# Buck_Boost_Converter.net
KiCad netlist of a schematic drawn in Altium Designer
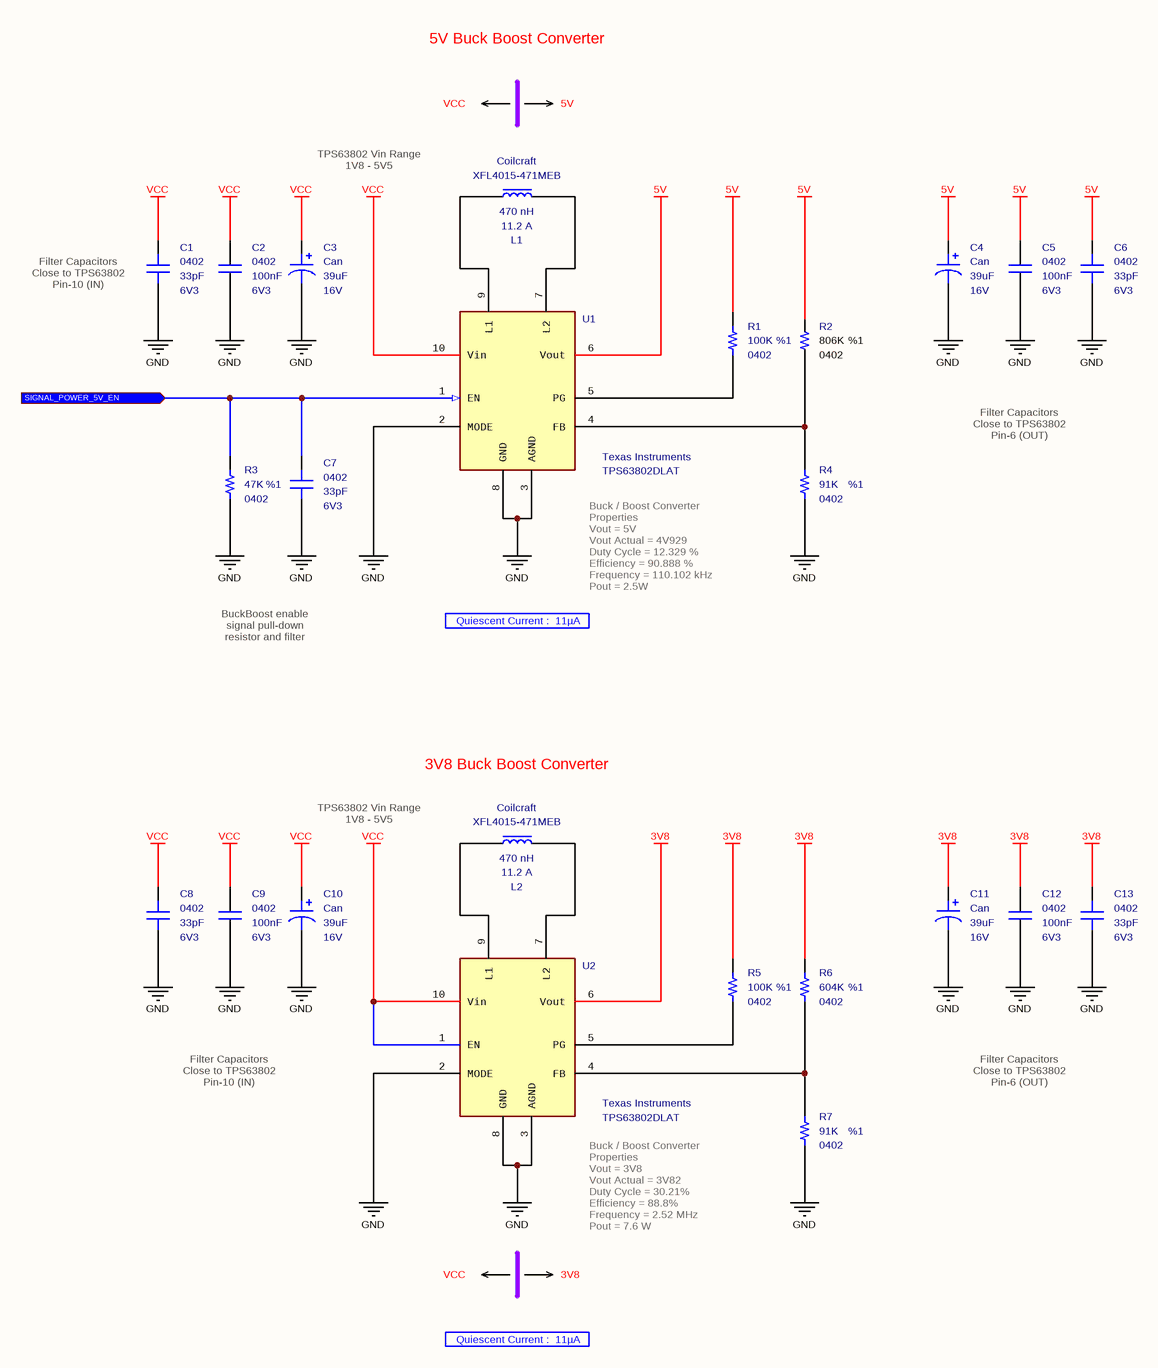
[diagram p0: Buck Boost Converter.SchDoc]

(export (version "E")
  (design (tool "Eeschema 10.0.6"))
  (components
    (comp (ref "C1")
      (value "33pF")
      (footprint "CAPACITOR_0402")
      (description "Capacitor - 33pF [0402] (Ceramic)")
      (fields
        (field (name "MANUFACTURER_PART_NUMBER") "C0402C330J9RACAUTO")
        (field (name "MOUSER_PART_NUMBER") "80-C0402C330J9RAUTO")
        (field (name "CASE") "0402")
        (field (name "VOLTAGE") "6V3")
      )
      (libsource (lib "Ovoo_Schematic") (part "Capacitor - 33pF [0402-6V3]"))
    )
    (comp (ref "C2")
      (value "100nF")
      (footprint "CAPACITOR_0402")
      (description "Capacitor - 100nF [0402-6V3] (Ceramic)")
      (fields
        (field (name "MANUFACTURER_PART_NUMBER") "04026D104KAT4A")
        (field (name "MOUSER_PART_NUMBER") "581-04026D104KAT4A")
        (field (name "CASE") "0402")
        (field (name "VOLTAGE") "6V3")
      )
      (libsource (lib "Ovoo_Schematic") (part "Capacitor - 100nF [0402-6V3]"))
    )
    (comp (ref "C3")
      (value "39uF")
      (footprint "CAPACITOR_CAN-B6")
      (description "Capacitor - 39uF 16V [Can] (Electrolytic)")
      (fields
        (field (name "MANUFACTURER_PART_NUMBER") "16SVPC39MV")
        (field (name "MOUSER_PART_NUMBER") "667-16SVPC39MV")
        (field (name "CASE") "Can")
        (field (name "VOLTAGE") "16V")
      )
      (libsource (lib "Ovoo_Schematic") (part "Capacitor - 39uF [Can-16V]"))
    )
    (comp (ref "C4")
      (value "39uF")
      (footprint "CAPACITOR_CAN-B6")
      (description "Capacitor - 39uF 16V [Can] (Electrolytic)")
      (fields
        (field (name "MANUFACTURER_PART_NUMBER") "16SVPC39MV")
        (field (name "MOUSER_PART_NUMBER") "667-16SVPC39MV")
        (field (name "CASE") "Can")
        (field (name "VOLTAGE") "16V")
      )
      (libsource (lib "Ovoo_Schematic") (part "Capacitor - 39uF [Can-16V]"))
    )
    (comp (ref "C5")
      (value "100nF")
      (footprint "CAPACITOR_0402")
      (description "Capacitor - 100nF [0402-6V3] (Ceramic)")
      (fields
        (field (name "MANUFACTURER_PART_NUMBER") "04026D104KAT4A")
        (field (name "MOUSER_PART_NUMBER") "581-04026D104KAT4A")
        (field (name "CASE") "0402")
        (field (name "VOLTAGE") "6V3")
      )
      (libsource (lib "Ovoo_Schematic") (part "Capacitor - 100nF [0402-6V3]"))
    )
    (comp (ref "C6")
      (value "33pF")
      (footprint "CAPACITOR_0402")
      (description "Capacitor - 33pF [0402] (Ceramic)")
      (fields
        (field (name "MANUFACTURER_PART_NUMBER") "C0402C330J9RACAUTO")
        (field (name "MOUSER_PART_NUMBER") "80-C0402C330J9RAUTO")
        (field (name "CASE") "0402")
        (field (name "VOLTAGE") "6V3")
      )
      (libsource (lib "Ovoo_Schematic") (part "Capacitor - 33pF [0402-6V3]"))
    )
    (comp (ref "C7")
      (value "33pF")
      (footprint "CAPACITOR_0402")
      (description "Capacitor - 33pF [0402] (Ceramic)")
      (fields
        (field (name "MANUFACTURER_PART_NUMBER") "C0402C330J9RACAUTO")
        (field (name "MOUSER_PART_NUMBER") "80-C0402C330J9RAUTO")
        (field (name "CASE") "0402")
        (field (name "VOLTAGE") "6V3")
      )
      (libsource (lib "Ovoo_Schematic") (part "Capacitor - 33pF [0402-6V3]"))
    )
    (comp (ref "C8")
      (value "33pF")
      (footprint "CAPACITOR_0402")
      (description "Capacitor - 33pF [0402] (Ceramic)")
      (fields
        (field (name "MANUFACTURER_PART_NUMBER") "C0402C330J9RACAUTO")
        (field (name "MOUSER_PART_NUMBER") "80-C0402C330J9RAUTO")
        (field (name "CASE") "0402")
        (field (name "VOLTAGE") "6V3")
      )
      (libsource (lib "Ovoo_Schematic") (part "Capacitor - 33pF [0402-6V3]"))
    )
    (comp (ref "C9")
      (value "100nF")
      (footprint "CAPACITOR_0402")
      (description "Capacitor - 100nF [0402-6V3] (Ceramic)")
      (fields
        (field (name "MANUFACTURER_PART_NUMBER") "04026D104KAT4A")
        (field (name "MOUSER_PART_NUMBER") "581-04026D104KAT4A")
        (field (name "CASE") "0402")
        (field (name "VOLTAGE") "6V3")
      )
      (libsource (lib "Ovoo_Schematic") (part "Capacitor - 100nF [0402-6V3]"))
    )
    (comp (ref "C10")
      (value "39uF")
      (footprint "CAPACITOR_CAN-B6")
      (description "Capacitor - 39uF 16V [Can] (Electrolytic)")
      (fields
        (field (name "MANUFACTURER_PART_NUMBER") "16SVPC39MV")
        (field (name "MOUSER_PART_NUMBER") "667-16SVPC39MV")
        (field (name "CASE") "Can")
        (field (name "VOLTAGE") "16V")
      )
      (libsource (lib "Ovoo_Schematic") (part "Capacitor - 39uF [Can-16V]"))
    )
    (comp (ref "C11")
      (value "39uF")
      (footprint "CAPACITOR_CAN-B6")
      (description "Capacitor - 39uF 16V [Can] (Electrolytic)")
      (fields
        (field (name "MANUFACTURER_PART_NUMBER") "16SVPC39MV")
        (field (name "MOUSER_PART_NUMBER") "667-16SVPC39MV")
        (field (name "CASE") "Can")
        (field (name "VOLTAGE") "16V")
      )
      (libsource (lib "Ovoo_Schematic") (part "Capacitor - 39uF [Can-16V]"))
    )
    (comp (ref "C12")
      (value "100nF")
      (footprint "CAPACITOR_0402")
      (description "Capacitor - 100nF [0402-6V3] (Ceramic)")
      (fields
        (field (name "MANUFACTURER_PART_NUMBER") "04026D104KAT4A")
        (field (name "MOUSER_PART_NUMBER") "581-04026D104KAT4A")
        (field (name "CASE") "0402")
        (field (name "VOLTAGE") "6V3")
      )
      (libsource (lib "Ovoo_Schematic") (part "Capacitor - 100nF [0402-6V3]"))
    )
    (comp (ref "C13")
      (value "33pF")
      (footprint "CAPACITOR_0402")
      (description "Capacitor - 33pF [0402] (Ceramic)")
      (fields
        (field (name "MANUFACTURER_PART_NUMBER") "C0402C330J9RACAUTO")
        (field (name "MOUSER_PART_NUMBER") "80-C0402C330J9RAUTO")
        (field (name "CASE") "0402")
        (field (name "VOLTAGE") "6V3")
      )
      (libsource (lib "Ovoo_Schematic") (part "Capacitor - 33pF [0402-6V3]"))
    )
    (comp (ref "L1")
      (value "470 nH")
      (footprint "INDUCTOR_XFL4015")
      (description "Fixed Inductors 0.47uH 20% 11.2A 8.36mOhms AEC-Q200")
      (fields
        (field (name "MOUSER_PART_NUMBER") "994-XFL4015-471MEB")
        (field (name "TOLERANCE") "20%")
        (field (name "MAXIMUM DC CURRENT") "11.2 A")
        (field (name "MANUFACTURER_PART_NUMBER") "XFL4015-471MEB")
        (field (name "MANUFACTURER_NAME") "Coilcraft")
      )
      (libsource (lib "Ovoo_Schematic") (part "Inductor - 470 nH [SMD]"))
    )
    (comp (ref "L2")
      (value "470 nH")
      (footprint "INDUCTOR_XFL4015")
      (description "Fixed Inductors 0.47uH 20% 11.2A 8.36mOhms AEC-Q200")
      (fields
        (field (name "MOUSER_PART_NUMBER") "994-XFL4015-471MEB")
        (field (name "TOLERANCE") "20%")
        (field (name "MAXIMUM DC CURRENT") "11.2 A")
        (field (name "MANUFACTURER_PART_NUMBER") "XFL4015-471MEB")
        (field (name "MANUFACTURER_NAME") "Coilcraft")
      )
      (libsource (lib "Ovoo_Schematic") (part "Inductor - 470 nH [SMD]"))
    )
    (comp (ref "R1")
      (value "100K")
      (footprint "RESISTOR_0402")
      (description "Thick Film Resistors - SMD 1/16 W 100 Kohms 1%")
      (fields
        (field (name "MANUFACTURER_PART_NUMBER") "CRCW0402100KFKED")
        (field (name "MOUSER_PART_NUMBER") "71-CRCW0402-100K-E3")
        (field (name "TOLERANCE") "%1")
        (field (name "CASE") "0402")
      )
      (libsource (lib "Ovoo_Schematic") (part "Resistor - 100K"))
    )
    (comp (ref "R2")
      (value "806K")
      (footprint "RESISTOR_0402")
      (description "Thick Film Resistors - SMD 1/16 W 806 Kohms 1%")
      (fields
        (field (name "TOLERANCE") "%1")
        (field (name "CASE") "0402")
        (field (name "MANUFACTURER PART NUMBER") "CRCW0402806KFKED")
        (field (name "MOUSER PART NUMBER") "71-CRCW0402-806K-E3")
      )
      (libsource (lib "Ovoo_Library") (part "Resistor - 806K"))
    )
    (comp (ref "R3")
      (value "47K")
      (footprint "RESISTOR_0402")
      (description "Thick Film Resistors - SMD 1/16 W 47 Kohms 1%")
      (fields
        (field (name "MANUFACTURER_PART_NUMBER") "CRCW040247K0FKED")
        (field (name "MOUSER_PART_NUMBER") "71-CRCW0402-47K-E3")
        (field (name "TOLERANCE") "%1")
        (field (name "CASE") "0402")
      )
      (libsource (lib "Ovoo_Schematic") (part "Resistor - 47K"))
    )
    (comp (ref "R4")
      (value "91K")
      (footprint "RESISTOR_0402")
      (description "Thick Film Resistors - SMD 1/16 W 91 Kohms 1%")
      (fields
        (field (name "MANUFACTURER_PART_NUMBER") "CRCW040291K0FKED")
        (field (name "MOUSER_PART_NUMBER") "71-CRCW040291K0FKED")
        (field (name "TOLERANCE") "%1")
        (field (name "CASE") "0402")
      )
      (libsource (lib "Ovoo_Schematic") (part "Resistor - 91K"))
    )
    (comp (ref "R5")
      (value "100K")
      (footprint "RESISTOR_0402")
      (description "Thick Film Resistors - SMD 1/16 W 100 Kohms 1%")
      (fields
        (field (name "MANUFACTURER_PART_NUMBER") "CRCW0402100KFKED")
        (field (name "MOUSER_PART_NUMBER") "71-CRCW0402-100K-E3")
        (field (name "TOLERANCE") "%1")
        (field (name "CASE") "0402")
      )
      (libsource (lib "Ovoo_Schematic") (part "Resistor - 100K"))
    )
    (comp (ref "R6")
      (value "604K")
      (footprint "RESISTOR_0402")
      (description "Thick Film Resistors - SMD 1/16 W 604 Kohms 1%")
      (fields
        (field (name "MANUFACTURER_PART_NUMBER") "CRCW0402604KFKED")
        (field (name "MOUSER_PART_NUMBER") "71-CRCW0402-604K-E3")
        (field (name "TOLERANCE") "%1")
        (field (name "CASE") "0402")
      )
      (libsource (lib "Ovoo_Schematic") (part "Resistor - 604K"))
    )
    (comp (ref "R7")
      (value "91K")
      (footprint "RESISTOR_0402")
      (description "Thick Film Resistors - SMD 1/16 W 91 Kohms 1%")
      (fields
        (field (name "MANUFACTURER_PART_NUMBER") "CRCW040291K0FKED")
        (field (name "MOUSER_PART_NUMBER") "71-CRCW040291K0FKED")
        (field (name "TOLERANCE") "%1")
        (field (name "CASE") "0402")
      )
      (libsource (lib "Ovoo_Schematic") (part "Resistor - 91K"))
    )
    (comp (ref "U1")
      (value "Buck-Boost Converter")
      (footprint "VSON-10")
      (fields
        (field (name "MOUSER_PART_NUMBER") "595-TPS63802DLAT")
        (field (name "MANUFACTURER_PART_NUMBER") "TPS63802DLAT")
        (field (name "MANUFACTURER_NAME") "Texas Instruments")
      )
      (libsource (lib "Ovoo_Schematic") (part "IC - TPS63802DLAT"))
    )
    (comp (ref "U2")
      (value "Buck-Boost Converter")
      (footprint "VSON-10")
      (fields
        (field (name "MOUSER_PART_NUMBER") "595-TPS63802DLAT")
        (field (name "MANUFACTURER_PART_NUMBER") "TPS63802DLAT")
        (field (name "MANUFACTURER_NAME") "Texas Instruments")
      )
      (libsource (lib "Ovoo_Schematic") (part "IC - TPS63802DLAT"))
    )
  )
  (nets
    (net (code "1") (name "/SIGNAL_POWER_5V_EN") (class "Default")
      (node (ref "C7") (pin "2") (pinfunction "2_2") (pintype "passive"))
      (node (ref "R3") (pin "2") (pinfunction "2_2") (pintype "passive"))
      (node (ref "U1") (pin "1") (pinfunction "EN_1") (pintype "input"))
    )
    (net (code "2") (name "3V8") (class "Default")
      (node (ref "C11") (pin "1") (pinfunction "1_1") (pintype "passive"))
      (node (ref "C12") (pin "1") (pinfunction "1_1") (pintype "passive"))
      (node (ref "C13") (pin "2") (pinfunction "2_2") (pintype "passive"))
      (node (ref "R5") (pin "2") (pinfunction "2_2") (pintype "passive"))
      (node (ref "R6") (pin "2") (pinfunction "2_2") (pintype "passive"))
      (node (ref "U2") (pin "6") (pinfunction "Vout_6") (pintype "power_in"))
    )
    (net (code "3") (name "5V") (class "Default")
      (node (ref "C4") (pin "1") (pinfunction "1_1") (pintype "passive"))
      (node (ref "C5") (pin "1") (pinfunction "1_1") (pintype "passive"))
      (node (ref "C6") (pin "2") (pinfunction "2_2") (pintype "passive"))
      (node (ref "R1") (pin "2") (pinfunction "2_2") (pintype "passive"))
      (node (ref "R2") (pin "2") (pinfunction "2_2") (pintype "passive"))
      (node (ref "U1") (pin "6") (pinfunction "Vout_6") (pintype "power_in"))
    )
    (net (code "4") (name "GND") (class "Default")
      (node (ref "C1") (pin "1") (pinfunction "1_1") (pintype "passive"))
      (node (ref "C10") (pin "2") (pinfunction "2_2") (pintype "passive"))
      (node (ref "C11") (pin "2") (pinfunction "2_2") (pintype "passive"))
      (node (ref "C12") (pin "2") (pinfunction "2_2") (pintype "passive"))
      (node (ref "C13") (pin "1") (pinfunction "1_1") (pintype "passive"))
      (node (ref "C2") (pin "2") (pinfunction "2_2") (pintype "passive"))
      (node (ref "C3") (pin "2") (pinfunction "2_2") (pintype "passive"))
      (node (ref "C4") (pin "2") (pinfunction "2_2") (pintype "passive"))
      (node (ref "C5") (pin "2") (pinfunction "2_2") (pintype "passive"))
      (node (ref "C6") (pin "1") (pinfunction "1_1") (pintype "passive"))
      (node (ref "C7") (pin "1") (pinfunction "1_1") (pintype "passive"))
      (node (ref "C8") (pin "1") (pinfunction "1_1") (pintype "passive"))
      (node (ref "C9") (pin "2") (pinfunction "2_2") (pintype "passive"))
      (node (ref "R3") (pin "1") (pinfunction "1_1") (pintype "passive"))
      (node (ref "R4") (pin "1") (pinfunction "1_1") (pintype "passive"))
      (node (ref "R7") (pin "1") (pinfunction "1_1") (pintype "passive"))
      (node (ref "U1") (pin "2") (pinfunction "MODE_2") (pintype "passive"))
      (node (ref "U1") (pin "3") (pinfunction "AGND_3") (pintype "power_in"))
      (node (ref "U1") (pin "8") (pinfunction "GND_8") (pintype "power_in"))
      (node (ref "U2") (pin "2") (pinfunction "MODE_2") (pintype "passive"))
      (node (ref "U2") (pin "3") (pinfunction "AGND_3") (pintype "power_in"))
      (node (ref "U2") (pin "8") (pinfunction "GND_8") (pintype "power_in"))
    )
    (net (code "5") (name "Net-(U1-FB)") (class "Default")
      (node (ref "R2") (pin "1") (pinfunction "1_1") (pintype "passive"))
      (node (ref "R4") (pin "2") (pinfunction "2_2") (pintype "passive"))
      (node (ref "U1") (pin "4") (pinfunction "FB_4") (pintype "passive"))
    )
    (net (code "6") (name "Net-(U1-L1)") (class "Default")
      (node (ref "L1") (pin "1") (pinfunction "1_1") (pintype "passive"))
      (node (ref "U1") (pin "9") (pinfunction "L1_9") (pintype "passive"))
    )
    (net (code "7") (name "Net-(U1-L2)") (class "Default")
      (node (ref "L1") (pin "2") (pinfunction "2_2") (pintype "passive"))
      (node (ref "U1") (pin "7") (pinfunction "L2_7") (pintype "passive"))
    )
    (net (code "8") (name "Net-(U1-PG)") (class "Default")
      (node (ref "R1") (pin "1") (pinfunction "1_1") (pintype "passive"))
      (node (ref "U1") (pin "5") (pinfunction "PG_5") (pintype "passive"))
    )
    (net (code "9") (name "Net-(U2-FB)") (class "Default")
      (node (ref "R6") (pin "1") (pinfunction "1_1") (pintype "passive"))
      (node (ref "R7") (pin "2") (pinfunction "2_2") (pintype "passive"))
      (node (ref "U2") (pin "4") (pinfunction "FB_4") (pintype "passive"))
    )
    (net (code "10") (name "Net-(U2-L1)") (class "Default")
      (node (ref "L2") (pin "1") (pinfunction "1_1") (pintype "passive"))
      (node (ref "U2") (pin "9") (pinfunction "L1_9") (pintype "passive"))
    )
    (net (code "11") (name "Net-(U2-L2)") (class "Default")
      (node (ref "L2") (pin "2") (pinfunction "2_2") (pintype "passive"))
      (node (ref "U2") (pin "7") (pinfunction "L2_7") (pintype "passive"))
    )
    (net (code "12") (name "Net-(U2-PG)") (class "Default")
      (node (ref "R5") (pin "1") (pinfunction "1_1") (pintype "passive"))
      (node (ref "U2") (pin "5") (pinfunction "PG_5") (pintype "passive"))
    )
    (net (code "13") (name "VCC") (class "Default")
      (node (ref "C1") (pin "2") (pinfunction "2_2") (pintype "passive"))
      (node (ref "C10") (pin "1") (pinfunction "1_1") (pintype "passive"))
      (node (ref "C2") (pin "1") (pinfunction "1_1") (pintype "passive"))
      (node (ref "C3") (pin "1") (pinfunction "1_1") (pintype "passive"))
      (node (ref "C8") (pin "2") (pinfunction "2_2") (pintype "passive"))
      (node (ref "C9") (pin "1") (pinfunction "1_1") (pintype "passive"))
      (node (ref "U1") (pin "10") (pinfunction "Vin_10") (pintype "power_in"))
      (node (ref "U2") (pin "1") (pinfunction "EN_1") (pintype "input"))
      (node (ref "U2") (pin "10") (pinfunction "Vin_10") (pintype "power_in"))
    )
  )
)
